# io.net
KiCad netlist of a schematic drawn in Altium Designer
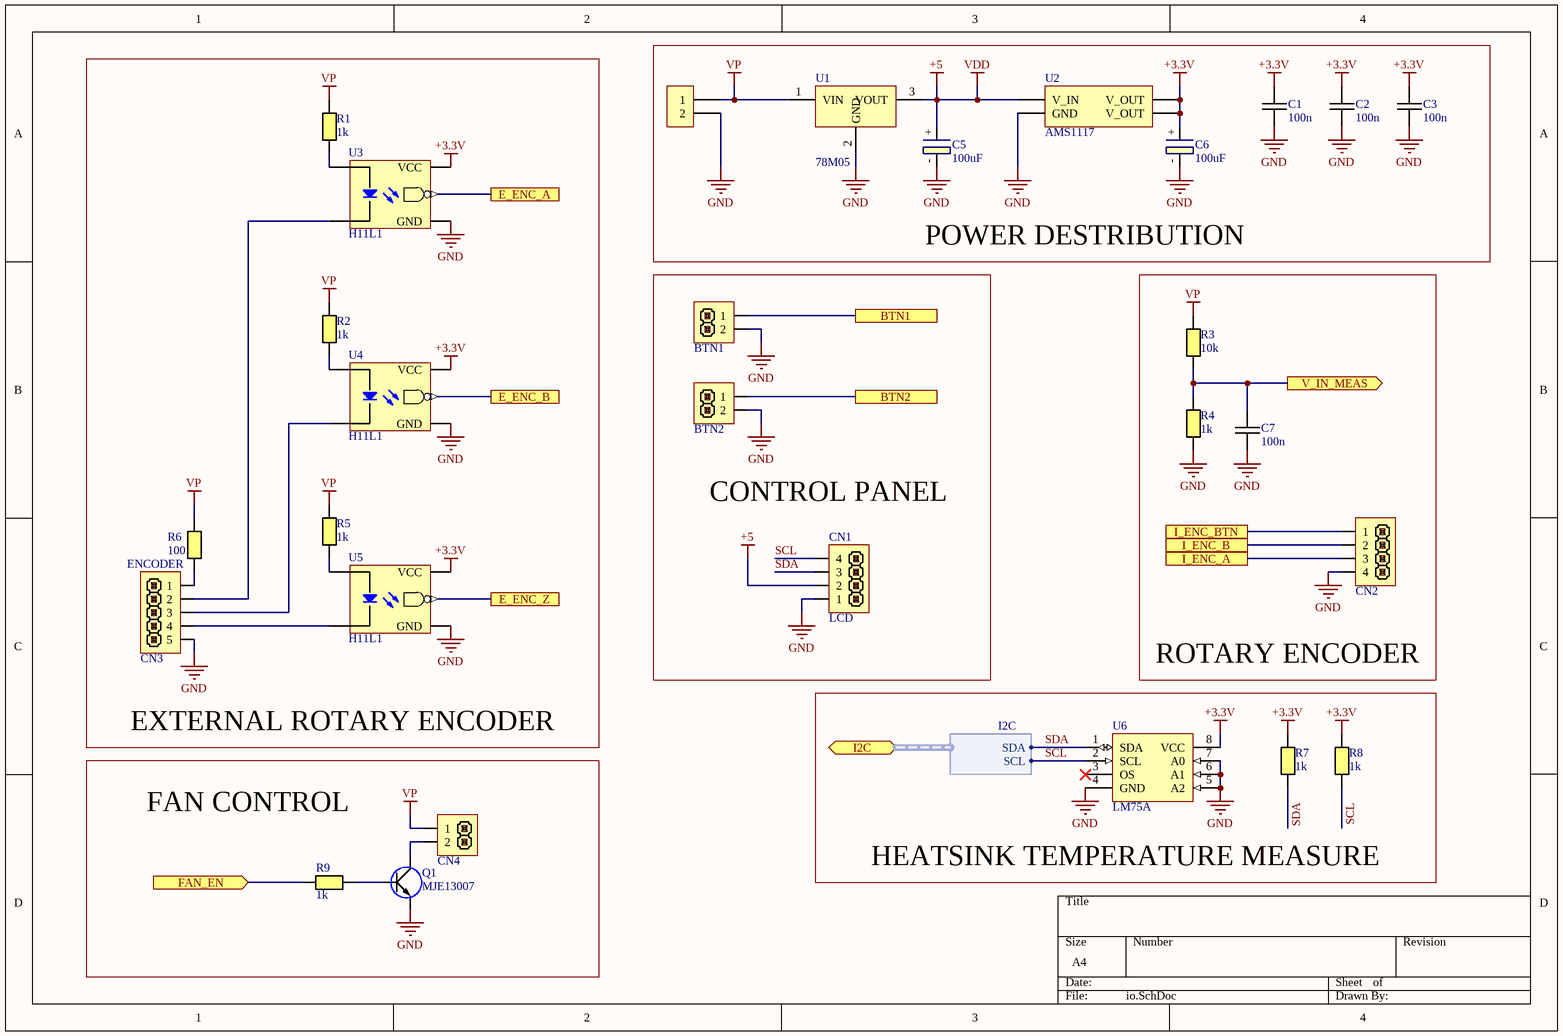
[diagram p0: io.SchDoc]

(export (version "E")
  (design (tool "Eeschema 10.0.6"))
  (components
    (comp (ref "BTN1")
      (value "PIN HEADER 1x2")
      (footprint "XH2.54 2P")
      (libsource (lib "Connectors") (part "PIN HEADER 2.54 1x2"))
    )
    (comp (ref "BTN2")
      (value "PIN HEADER 1x2")
      (footprint "XH2.54 2P")
      (libsource (lib "Connectors") (part "PIN HEADER 2.54 1x2"))
    )
    (comp (ref "C1")
      (value "100n")
      (footprint "CAPC0603(1608)55_N")
      (description "Ceramic capacitor Medium density")
      (libsource (lib "Discrete") (part "Capacitor M"))
    )
    (comp (ref "C2")
      (value "100n")
      (footprint "CAPC0603(1608)55_N")
      (description "Ceramic capacitor Medium density")
      (libsource (lib "Discrete") (part "Capacitor M"))
    )
    (comp (ref "C3")
      (value "100n")
      (footprint "CAPC0603(1608)55_N")
      (description "Ceramic capacitor Medium density")
      (libsource (lib "Discrete") (part "Capacitor M"))
    )
    (comp (ref "C5")
      (value "100uF")
      (footprint "TC7343")
      (description "Capacitor Electrolitic")
      (libsource (lib "Discrete") (part "Capacitor Electrolitic"))
    )
    (comp (ref "C6")
      (value "100uF")
      (footprint "TC7343")
      (description "Capacitor Electrolitic")
      (libsource (lib "Discrete") (part "Capacitor Electrolitic"))
    )
    (comp (ref "C7")
      (value "100n")
      (footprint "CAPC0603(1608)55_N")
      (description "Ceramic capacitor Medium density")
      (libsource (lib "Discrete") (part "Capacitor M"))
    )
    (comp (ref "CN1")
      (value "LCD")
      (footprint "XH2.54 4P")
      (libsource (lib "Connectors") (part "PIN HEADER 2.54 1x4"))
    )
    (comp (ref "CN2")
      (value "PIN HEADER 1x4")
      (footprint "XH2.54 4P")
      (libsource (lib "Connectors") (part "PIN HEADER 2.54 1x4"))
    )
    (comp (ref "CN3")
      (value "ENCODER")
      (footprint "XH2.54 5P")
      (libsource (lib "Connectors") (part "PIN HEADER 2.54 1x5"))
    )
    (comp (ref "CN4")
      (value "PIN HEADER 1x2")
      (footprint "XH2.54 2P")
      (libsource (lib "") (part "PIN HEADER 2.54 1x2_1"))
    )
    (comp (ref "PWR1")
      (value "TBLOCK-M2")
      (footprint "TBLOCK-M2")
      (libsource (lib "Connectors") (part "TBLOCK-M2"))
    )
    (comp (ref "Q1")
      (value "MJE13007")
      (footprint "TO-220-3 H")
      (description "Switch-mode NPN Bipolar  Power Transistor")
      (libsource (lib "Transistors") (part "MJE13007"))
    )
    (comp (ref "R1")
      (value "1k")
      (footprint "RESC0603(1608)_N")
      (description "Resistor Medium Density")
      (libsource (lib "Discrete") (part "Resistor M"))
    )
    (comp (ref "R2")
      (value "1k")
      (footprint "RESC0603(1608)_N")
      (description "Resistor Medium Density")
      (libsource (lib "Discrete") (part "Resistor M"))
    )
    (comp (ref "R3")
      (value "10k")
      (footprint "RESC0603(1608)_N")
      (description "Resistor Medium Density")
      (libsource (lib "Discrete") (part "Resistor M"))
    )
    (comp (ref "R4")
      (value "1k")
      (footprint "RESC0603(1608)_N")
      (description "Resistor Medium Density")
      (libsource (lib "Discrete") (part "Resistor M"))
    )
    (comp (ref "R5")
      (value "1k")
      (footprint "RESC0603(1608)_N")
      (description "Resistor Medium Density")
      (libsource (lib "Discrete") (part "Resistor M"))
    )
    (comp (ref "R6")
      (value "100")
      (footprint "RESC0603(1608)_N")
      (description "Resistor Medium Density")
      (libsource (lib "Discrete") (part "Resistor M"))
    )
    (comp (ref "R7")
      (value "1k")
      (footprint "RESC0603(1608)_N")
      (description "Resistor Medium Density")
      (libsource (lib "Discrete") (part "Resistor M"))
    )
    (comp (ref "R8")
      (value "1k")
      (footprint "RESC0603(1608)_N")
      (description "Resistor Medium Density")
      (libsource (lib "Discrete") (part "Resistor M"))
    )
    (comp (ref "R9")
      (value "1k")
      (footprint "RESC0603(1608)_N")
      (description "Resistor Medium Density")
      (libsource (lib "") (part "Resistor M_1"))
    )
    (comp (ref "U1")
      (value "78M05")
      (footprint "TO-252")
      (description "Linear Voltage Regulator")
      (libsource (lib "VoltageRegulators") (part "78M05"))
    )
    (comp (ref "U2")
      (value "AMS1117")
      (footprint "SOT229P700X180-4N")
      (description "800mA LDO  15V max")
      (libsource (lib "VoltageRegulators") (part "AMS1117"))
    )
    (comp (ref "U3") (value "H11L1") (footprint "DIP06") (libsource (lib "Optical") (part "H11L1")))
    (comp (ref "U4") (value "H11L1") (footprint "DIP06") (libsource (lib "Optical") (part "H11L1")))
    (comp (ref "U5") (value "H11L1") (footprint "DIP06") (libsource (lib "Optical") (part "H11L1")))
    (comp (ref "U6")
      (value "LM75A")
      (footprint "SO8")
      (description "Digital temperature sensor")
      (libsource (lib "Sensors") (part "LM75A"))
    )
  )
  (nets
    (net (code "2") (name "+3.3V") (class "Default")
      (node (ref "C1") (pin "1") (pinfunction "1_1") (pintype "passive"))
      (node (ref "C2") (pin "1") (pinfunction "1_1") (pintype "passive"))
      (node (ref "C3") (pin "1") (pinfunction "1_1") (pintype "passive"))
      (node (ref "C6") (pin "+") (pinfunction "+_+") (pintype "passive"))
      (node (ref "R7") (pin "2") (pinfunction "2_2") (pintype "passive"))
      (node (ref "R8") (pin "2") (pinfunction "2_2") (pintype "passive"))
      (node (ref "U2") (pin "2") (pinfunction "V_OUT_2") (pintype "passive"))
      (node (ref "U2") (pin "4") (pinfunction "V_OUT_4") (pintype "passive"))
      (node (ref "U3") (pin "6") (pinfunction "VCC_6") (pintype "power_in"))
      (node (ref "U4") (pin "6") (pinfunction "VCC_6") (pintype "power_in"))
      (node (ref "U5") (pin "6") (pinfunction "VCC_6") (pintype "power_in"))
      (node (ref "U6") (pin "8") (pinfunction "VCC_8") (pintype "power_in"))
    )
    (net (code "3") (name "+5") (class "Default")
      (node (ref "C5") (pin "+") (pinfunction "+_+") (pintype "passive"))
      (node (ref "CN1") (pin "2") (pinfunction "2_2") (pintype "passive"))
      (node (ref "U1") (pin "3") (pinfunction "VOUT_3") (pintype "power_in"))
      (node (ref "U2") (pin "3") (pinfunction "V_IN_3") (pintype "passive"))
    )
    (net (code "4") (name "/BTN1") (class "Default")
      (node (ref "BTN1") (pin "1") (pinfunction "1_1") (pintype "passive"))
    )
    (net (code "5") (name "/BTN2") (class "Default")
      (node (ref "BTN2") (pin "1") (pinfunction "1_1") (pintype "passive"))
    )
    (net (code "6") (name "/E_ENC_A") (class "Default")
      (node (ref "U3") (pin "4") (pinfunction "Vo_4") (pintype "output"))
    )
    (net (code "7") (name "/E_ENC_B") (class "Default")
      (node (ref "U4") (pin "4") (pinfunction "Vo_4") (pintype "output"))
    )
    (net (code "8") (name "/E_ENC_Z") (class "Default")
      (node (ref "U5") (pin "4") (pinfunction "Vo_4") (pintype "output"))
    )
    (net (code "9") (name "/FAN_EN") (class "Default")
      (node (ref "R9") (pin "1") (pinfunction "1_1") (pintype "passive"))
    )
    (net (code "10") (name "/I_ENC_A") (class "Default")
      (node (ref "CN2") (pin "3") (pinfunction "3_3") (pintype "passive"))
    )
    (net (code "11") (name "/I_ENC_B") (class "Default")
      (node (ref "CN2") (pin "2") (pinfunction "2_2") (pintype "passive"))
    )
    (net (code "12") (name "/I_ENC_BTN") (class "Default")
      (node (ref "CN2") (pin "1") (pinfunction "1_1") (pintype "passive"))
    )
    (net (code "13") (name "/SCL") (class "Default")
      (node (ref "CN1") (pin "4") (pinfunction "4_4") (pintype "passive"))
      (node (ref "R8") (pin "1") (pinfunction "1_1") (pintype "passive"))
      (node (ref "U6") (pin "2") (pinfunction "SCL_2") (pintype "input"))
    )
    (net (code "14") (name "/SDA") (class "Default")
      (node (ref "CN1") (pin "3") (pinfunction "3_3") (pintype "passive"))
      (node (ref "R7") (pin "1") (pinfunction "1_1") (pintype "passive"))
      (node (ref "U6") (pin "1") (pinfunction "SDA_1") (pintype "bidirectional"))
    )
    (net (code "15") (name "/V_IN_MEAS") (class "Default")
      (node (ref "C7") (pin "1") (pinfunction "1_1") (pintype "passive"))
      (node (ref "R3") (pin "1") (pinfunction "1_1") (pintype "passive"))
      (node (ref "R4") (pin "2") (pinfunction "2_2") (pintype "passive"))
    )
    (net (code "17") (name "GND") (class "Default")
      (node (ref "BTN1") (pin "2") (pinfunction "2_2") (pintype "passive"))
      (node (ref "BTN2") (pin "2") (pinfunction "2_2") (pintype "passive"))
      (node (ref "C1") (pin "2") (pinfunction "2_2") (pintype "passive"))
      (node (ref "C2") (pin "2") (pinfunction "2_2") (pintype "passive"))
      (node (ref "C3") (pin "2") (pinfunction "2_2") (pintype "passive"))
      (node (ref "C5") (pin "-") (pinfunction "-_-") (pintype "passive"))
      (node (ref "C6") (pin "-") (pinfunction "-_-") (pintype "passive"))
      (node (ref "C7") (pin "2") (pinfunction "2_2") (pintype "passive"))
      (node (ref "CN1") (pin "1") (pinfunction "1_1") (pintype "passive"))
      (node (ref "CN2") (pin "4") (pinfunction "4_4") (pintype "passive"))
      (node (ref "CN3") (pin "5") (pinfunction "5_5") (pintype "passive"))
      (node (ref "PWR1") (pin "2") (pinfunction "2_2") (pintype "passive"))
      (node (ref "Q1") (pin "3") (pinfunction "E_3") (pintype "passive"))
      (node (ref "R4") (pin "1") (pinfunction "1_1") (pintype "passive"))
      (node (ref "U1") (pin "2") (pinfunction "GND_2") (pintype "passive"))
      (node (ref "U2") (pin "1") (pinfunction "GND_1") (pintype "passive"))
      (node (ref "U3") (pin "5") (pinfunction "GND_5") (pintype "power_in"))
      (node (ref "U4") (pin "5") (pinfunction "GND_5") (pintype "power_in"))
      (node (ref "U5") (pin "5") (pinfunction "GND_5") (pintype "power_in"))
      (node (ref "U6") (pin "4") (pinfunction "GND_4") (pintype "power_in"))
      (node (ref "U6") (pin "5") (pinfunction "A2_5") (pintype "input"))
      (node (ref "U6") (pin "6") (pinfunction "A1_6") (pintype "input"))
      (node (ref "U6") (pin "7") (pinfunction "A0_7") (pintype "input"))
    )
    (net (code "18") (name "Net-(CN3-Pad1)") (class "Default")
      (node (ref "CN3") (pin "1") (pinfunction "1_1") (pintype "passive"))
      (node (ref "R6") (pin "1") (pinfunction "1_1") (pintype "passive"))
    )
    (net (code "19") (name "Net-(Q1-B)") (class "Default")
      (node (ref "Q1") (pin "1") (pinfunction "B_1") (pintype "passive"))
      (node (ref "R9") (pin "2") (pinfunction "2_2") (pintype "passive"))
    )
    (net (code "20") (name "Net-(Q1-C)") (class "Default")
      (node (ref "CN4") (pin "2") (pinfunction "2_2") (pintype "passive"))
      (node (ref "Q1") (pin "2") (pinfunction "C_2") (pintype "passive"))
    )
    (net (code "21") (name "Net-(U3-A)") (class "Default")
      (node (ref "R1") (pin "1") (pinfunction "1_1") (pintype "passive"))
      (node (ref "U3") (pin "1") (pinfunction "A_1") (pintype "passive"))
    )
    (net (code "22") (name "Net-(U3-C)") (class "Default")
      (node (ref "CN3") (pin "2") (pinfunction "2_2") (pintype "passive"))
      (node (ref "U3") (pin "2") (pinfunction "C_2") (pintype "passive"))
    )
    (net (code "23") (name "Net-(U4-A)") (class "Default")
      (node (ref "R2") (pin "1") (pinfunction "1_1") (pintype "passive"))
      (node (ref "U4") (pin "1") (pinfunction "A_1") (pintype "passive"))
    )
    (net (code "24") (name "Net-(U4-C)") (class "Default")
      (node (ref "CN3") (pin "3") (pinfunction "3_3") (pintype "passive"))
      (node (ref "U4") (pin "2") (pinfunction "C_2") (pintype "passive"))
    )
    (net (code "25") (name "Net-(U5-A)") (class "Default")
      (node (ref "R5") (pin "1") (pinfunction "1_1") (pintype "passive"))
      (node (ref "U5") (pin "1") (pinfunction "A_1") (pintype "passive"))
    )
    (net (code "26") (name "Net-(U5-C)") (class "Default")
      (node (ref "CN3") (pin "4") (pinfunction "4_4") (pintype "passive"))
      (node (ref "U5") (pin "2") (pinfunction "C_2") (pintype "passive"))
    )
    (net (code "27") (name "VP") (class "Default")
      (node (ref "CN4") (pin "1") (pinfunction "1_1") (pintype "passive"))
      (node (ref "PWR1") (pin "1") (pinfunction "1_1") (pintype "passive"))
      (node (ref "R1") (pin "2") (pinfunction "2_2") (pintype "passive"))
      (node (ref "R2") (pin "2") (pinfunction "2_2") (pintype "passive"))
      (node (ref "R3") (pin "2") (pinfunction "2_2") (pintype "passive"))
      (node (ref "R5") (pin "2") (pinfunction "2_2") (pintype "passive"))
      (node (ref "R6") (pin "2") (pinfunction "2_2") (pintype "passive"))
      (node (ref "U1") (pin "1") (pinfunction "VIN_1") (pintype "power_in"))
    )
    (net (code "28") (name "unconnected-(U6-OS-Pad3)") (class "Default")
      (node (ref "U6") (pin "3") (pinfunction "OS_3") (pintype "open_collector+no_connect"))
    )
  )
)
